# TopBoard.net
KiCad netlist of a schematic drawn in Altium Designer
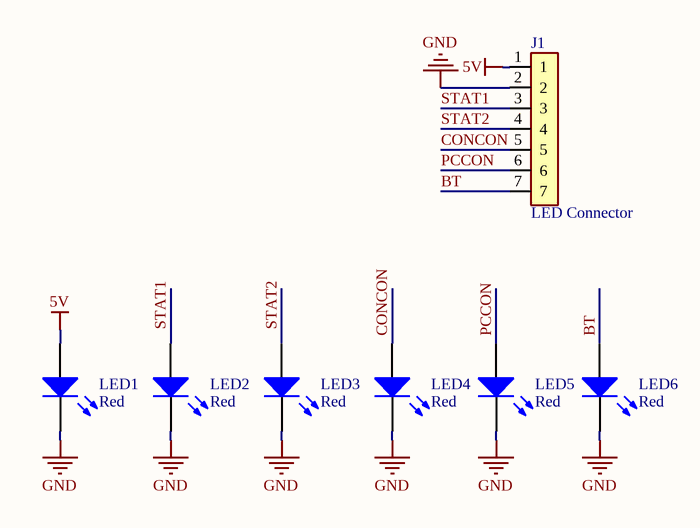
[diagram p0: TopBoard.SchDoc]

(export (version "E")
  (design (tool "Eeschema 10.0.6"))
  (components
    (comp (ref "J1")
      (value "LED Connector")
      (footprint "SamacSys:HDRV7W64P0X254_1X7_1778X254X869P")
      (description "Connector")
      (fields
        (field (name "MANUFACTURER_PART_NUMBER") "61300711121")
        (field (name "MOUSER PART NUMBER") "710-61300711121")
      )
      (libsource (lib "SamacSys") (part "61300711121"))
    )
    (comp (ref "LED1")
      (value "Red")
      (footprint "1206_A")
      (description "SMD mono-color Chip LED, WL-SMCW, Green")
      (fields (field (name "MANUFACTURER") "Wuerth Elektronik") (field (name "PARTNUMBER") "150120GS75000"))
      (libsource (lib "Altium Content Vault") (part "WE-LED_K1A2-2"))
    )
    (comp (ref "LED2")
      (value "Red")
      (footprint "1206_A")
      (description "SMD mono-color Chip LED, WL-SMCW, Green")
      (fields (field (name "MANUFACTURER") "Wuerth Elektronik") (field (name "PARTNUMBER") "150120GS75000"))
      (libsource (lib "Altium Content Vault") (part "WE-LED_K1A2-2"))
    )
    (comp (ref "LED3")
      (value "Red")
      (footprint "1206_A")
      (description "SMD mono-color Chip LED, WL-SMCW, Green")
      (fields (field (name "MANUFACTURER") "Wuerth Elektronik") (field (name "PARTNUMBER") "150120GS75000"))
      (libsource (lib "Altium Content Vault") (part "WE-LED_K1A2-2"))
    )
    (comp (ref "LED4")
      (value "Red")
      (footprint "1206_A")
      (description "SMD mono-color Chip LED, WL-SMCW, Green")
      (fields (field (name "MANUFACTURER") "Wuerth Elektronik") (field (name "PARTNUMBER") "150120GS75000"))
      (libsource (lib "Altium Content Vault") (part "WE-LED_K1A2-2"))
    )
    (comp (ref "LED5")
      (value "Red")
      (footprint "1206_A")
      (description "SMD mono-color Chip LED, WL-SMCW, Green")
      (fields (field (name "MANUFACTURER") "Wuerth Elektronik") (field (name "PARTNUMBER") "150120GS75000"))
      (libsource (lib "Altium Content Vault") (part "WE-LED_K1A2-2"))
    )
    (comp (ref "LED6")
      (value "Red")
      (footprint "1206_A")
      (description "SMD mono-color Chip LED, WL-SMCW, Green")
      (fields (field (name "MANUFACTURER") "Wuerth Elektronik") (field (name "PARTNUMBER") "150120GS75000"))
      (libsource (lib "Altium Content Vault") (part "WE-LED_K1A2-2"))
    )
  )
  (nets
    (net (code "1") (name "/BT") (class "Default")
      (node (ref "J1") (pin "7") (pinfunction "7_7") (pintype "passive"))
      (node (ref "LED6") (pin "2") (pinfunction "A_2") (pintype "passive"))
    )
    (net (code "2") (name "/CONCON") (class "Default")
      (node (ref "J1") (pin "5") (pinfunction "5_5") (pintype "passive"))
      (node (ref "LED4") (pin "2") (pinfunction "A_2") (pintype "passive"))
    )
    (net (code "3") (name "/PCCON") (class "Default")
      (node (ref "J1") (pin "6") (pinfunction "6_6") (pintype "passive"))
      (node (ref "LED5") (pin "2") (pinfunction "A_2") (pintype "passive"))
    )
    (net (code "4") (name "/STAT1") (class "Default")
      (node (ref "J1") (pin "3") (pinfunction "3_3") (pintype "passive"))
      (node (ref "LED2") (pin "2") (pinfunction "A_2") (pintype "passive"))
    )
    (net (code "5") (name "/STAT2") (class "Default")
      (node (ref "J1") (pin "4") (pinfunction "4_4") (pintype "passive"))
      (node (ref "LED3") (pin "2") (pinfunction "A_2") (pintype "passive"))
    )
    (net (code "6") (name "5V") (class "Default")
      (node (ref "J1") (pin "1") (pinfunction "1_1") (pintype "passive"))
      (node (ref "LED1") (pin "2") (pinfunction "A_2") (pintype "passive"))
    )
    (net (code "7") (name "GND") (class "Default")
      (node (ref "J1") (pin "2") (pinfunction "2_2") (pintype "passive"))
      (node (ref "LED1") (pin "1") (pinfunction "K_1") (pintype "passive"))
      (node (ref "LED2") (pin "1") (pinfunction "K_1") (pintype "passive"))
      (node (ref "LED3") (pin "1") (pinfunction "K_1") (pintype "passive"))
      (node (ref "LED4") (pin "1") (pinfunction "K_1") (pintype "passive"))
      (node (ref "LED5") (pin "1") (pinfunction "K_1") (pintype "passive"))
      (node (ref "LED6") (pin "1") (pinfunction "K_1") (pintype "passive"))
    )
  )
)
